# EEPROM_Programmer.net
KiCad netlist of a schematic drawn in Altium Designer
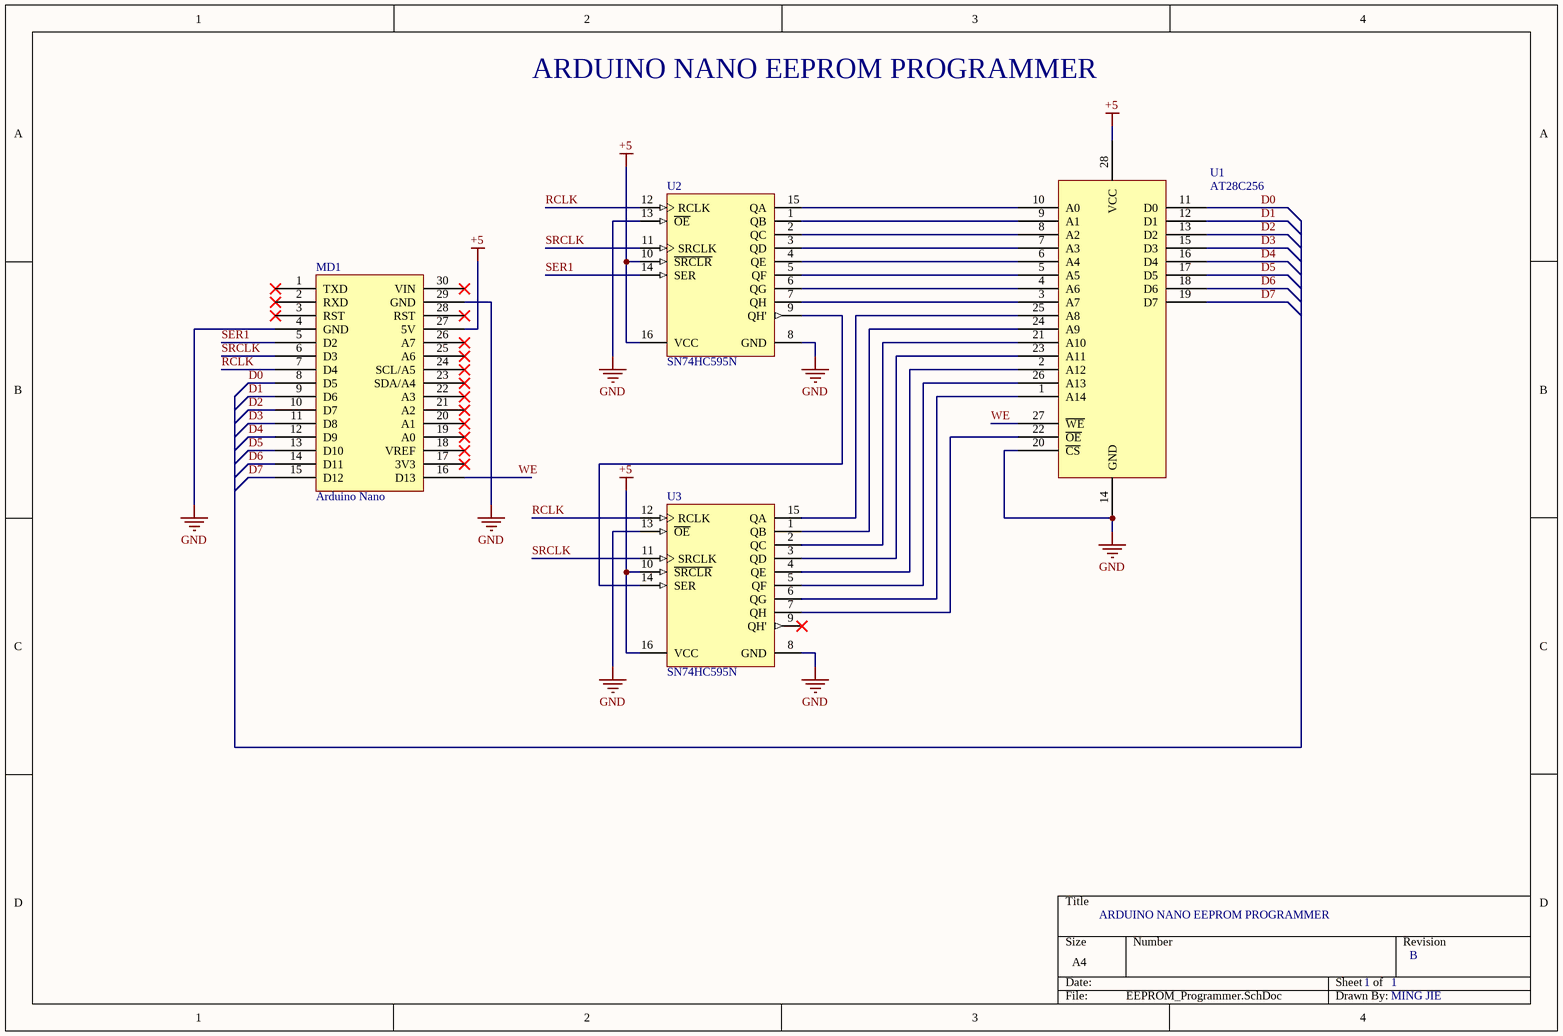
[diagram p0: EEPROM_Programmer.SchDoc]

(export (version "E")
  (design (tool "Eeschema 10.0.6"))
  (components
    (comp (ref "MD1")
      (value "Arduino Nano")
      (footprint "ARDUINO_NANO")
      (description "Arduino Nano board")
      (libsource (lib "6502_lib") (part "Arduino_Nano"))
    )
    (comp (ref "U1")
      (value "AT28C256")
      (footprint "DIP_28")
      (description "Paged Parallel EEPROM AT28C256")
      (libsource (lib "6502_lib") (part "AT28C256"))
    )
    (comp (ref "U2")
      (value "SN74HC595N")
      (footprint "N0016A")
      (description "8-Bit Shift Registers With 3-State Output Registers, N0016A, TUBE")
      (fields
        (field (name "GENERIC PART NUMBER") "SN74HC595")
        (field (name "MANUFACTURER") "Texas Instruments")
      )
      (libsource (lib "Altium Content Vault") (part "TI-SN74XHCT595X_SN74LV595A-16"))
    )
    (comp (ref "U3")
      (value "SN74HC595N")
      (footprint "N0016A")
      (description "8-Bit Shift Registers With 3-State Output Registers, N0016A, TUBE")
      (fields
        (field (name "GENERIC PART NUMBER") "SN74HC595")
        (field (name "MANUFACTURER") "Texas Instruments")
      )
      (libsource (lib "Altium Content Vault") (part "TI-SN74XHCT595X_SN74LV595A-16"))
    )
  )
  (nets
    (net (code "1") (name "+5") (class "Default")
      (node (ref "MD1") (pin "27") (pinfunction "5V_27") (pintype "passive"))
      (node (ref "U1") (pin "28") (pinfunction "VCC_28") (pintype "passive"))
      (node (ref "U2") (pin "10") (pinfunction "~{SRCLR}_10") (pintype "input"))
      (node (ref "U2") (pin "16") (pinfunction "VCC_16") (pintype "power_in"))
      (node (ref "U3") (pin "10") (pinfunction "~{SRCLR}_10") (pintype "input"))
      (node (ref "U3") (pin "16") (pinfunction "VCC_16") (pintype "power_in"))
    )
    (net (code "2") (name "/D0") (class "Default")
      (node (ref "MD1") (pin "8") (pinfunction "D5_8") (pintype "passive"))
      (node (ref "U1") (pin "11") (pinfunction "D0_11") (pintype "passive"))
    )
    (net (code "3") (name "/D1") (class "Default")
      (node (ref "MD1") (pin "9") (pinfunction "D6_9") (pintype "passive"))
      (node (ref "U1") (pin "12") (pinfunction "D1_12") (pintype "passive"))
    )
    (net (code "4") (name "/D2") (class "Default")
      (node (ref "MD1") (pin "10") (pinfunction "D7_10") (pintype "passive"))
      (node (ref "U1") (pin "13") (pinfunction "D2_13") (pintype "passive"))
    )
    (net (code "5") (name "/D3") (class "Default")
      (node (ref "MD1") (pin "11") (pinfunction "D8_11") (pintype "passive"))
      (node (ref "U1") (pin "15") (pinfunction "D3_15") (pintype "passive"))
    )
    (net (code "6") (name "/D4") (class "Default")
      (node (ref "MD1") (pin "12") (pinfunction "D9_12") (pintype "passive"))
      (node (ref "U1") (pin "16") (pinfunction "D4_16") (pintype "passive"))
    )
    (net (code "7") (name "/D5") (class "Default")
      (node (ref "MD1") (pin "13") (pinfunction "D10_13") (pintype "passive"))
      (node (ref "U1") (pin "17") (pinfunction "D5_17") (pintype "passive"))
    )
    (net (code "8") (name "/D6") (class "Default")
      (node (ref "MD1") (pin "14") (pinfunction "D11_14") (pintype "passive"))
      (node (ref "U1") (pin "18") (pinfunction "D6_18") (pintype "passive"))
    )
    (net (code "9") (name "/D7") (class "Default")
      (node (ref "MD1") (pin "15") (pinfunction "D12_15") (pintype "passive"))
      (node (ref "U1") (pin "19") (pinfunction "D7_19") (pintype "passive"))
    )
    (net (code "10") (name "/RCLK") (class "Default")
      (node (ref "MD1") (pin "7") (pinfunction "D4_7") (pintype "passive"))
      (node (ref "U2") (pin "12") (pinfunction "RCLK_12") (pintype "input"))
      (node (ref "U3") (pin "12") (pinfunction "RCLK_12") (pintype "input"))
    )
    (net (code "11") (name "/SER1") (class "Default")
      (node (ref "MD1") (pin "5") (pinfunction "D2_5") (pintype "passive"))
      (node (ref "U2") (pin "14") (pinfunction "SER_14") (pintype "input"))
    )
    (net (code "12") (name "/SRCLK") (class "Default")
      (node (ref "MD1") (pin "6") (pinfunction "D3_6") (pintype "passive"))
      (node (ref "U2") (pin "11") (pinfunction "SRCLK_11") (pintype "input"))
      (node (ref "U3") (pin "11") (pinfunction "SRCLK_11") (pintype "input"))
    )
    (net (code "13") (name "/WE") (class "Default")
      (node (ref "MD1") (pin "16") (pinfunction "D13_16") (pintype "passive"))
      (node (ref "U1") (pin "27") (pinfunction "~{WE}_27") (pintype "passive"))
    )
    (net (code "14") (name "GND") (class "Default")
      (node (ref "MD1") (pin "29") (pinfunction "GND_29") (pintype "passive"))
      (node (ref "MD1") (pin "4") (pinfunction "GND_4") (pintype "passive"))
      (node (ref "U1") (pin "14") (pinfunction "GND_14") (pintype "passive"))
      (node (ref "U1") (pin "20") (pinfunction "~{CS}_20") (pintype "passive"))
      (node (ref "U2") (pin "13") (pinfunction "~{OE}_13") (pintype "input"))
      (node (ref "U2") (pin "8") (pinfunction "GND_8") (pintype "power_in"))
      (node (ref "U3") (pin "13") (pinfunction "~{OE}_13") (pintype "input"))
      (node (ref "U3") (pin "8") (pinfunction "GND_8") (pintype "power_in"))
    )
    (net (code "15") (name "Net-(U1-A0)") (class "Default")
      (node (ref "U1") (pin "10") (pinfunction "A0_10") (pintype "passive"))
      (node (ref "U2") (pin "15") (pinfunction "QA_15") (pintype "tri_state"))
    )
    (net (code "16") (name "Net-(U1-A1)") (class "Default")
      (node (ref "U1") (pin "9") (pinfunction "A1_9") (pintype "passive"))
      (node (ref "U2") (pin "1") (pinfunction "QB_1") (pintype "tri_state"))
    )
    (net (code "17") (name "Net-(U1-A2)") (class "Default")
      (node (ref "U1") (pin "8") (pinfunction "A2_8") (pintype "passive"))
      (node (ref "U2") (pin "2") (pinfunction "QC_2") (pintype "tri_state"))
    )
    (net (code "18") (name "Net-(U1-A3)") (class "Default")
      (node (ref "U1") (pin "7") (pinfunction "A3_7") (pintype "passive"))
      (node (ref "U2") (pin "3") (pinfunction "QD_3") (pintype "tri_state"))
    )
    (net (code "19") (name "Net-(U1-A4)") (class "Default")
      (node (ref "U1") (pin "6") (pinfunction "A4_6") (pintype "passive"))
      (node (ref "U2") (pin "4") (pinfunction "QE_4") (pintype "tri_state"))
    )
    (net (code "20") (name "Net-(U1-A5)") (class "Default")
      (node (ref "U1") (pin "5") (pinfunction "A5_5") (pintype "passive"))
      (node (ref "U2") (pin "5") (pinfunction "QF_5") (pintype "tri_state"))
    )
    (net (code "21") (name "Net-(U1-A6)") (class "Default")
      (node (ref "U1") (pin "4") (pinfunction "A6_4") (pintype "passive"))
      (node (ref "U2") (pin "6") (pinfunction "QG_6") (pintype "tri_state"))
    )
    (net (code "22") (name "Net-(U1-A7)") (class "Default")
      (node (ref "U1") (pin "3") (pinfunction "A7_3") (pintype "passive"))
      (node (ref "U2") (pin "7") (pinfunction "QH_7") (pintype "tri_state"))
    )
    (net (code "23") (name "Net-(U1-A8)") (class "Default")
      (node (ref "U1") (pin "25") (pinfunction "A8_25") (pintype "passive"))
      (node (ref "U3") (pin "15") (pinfunction "QA_15") (pintype "tri_state"))
    )
    (net (code "24") (name "Net-(U1-A9)") (class "Default")
      (node (ref "U1") (pin "24") (pinfunction "A9_24") (pintype "passive"))
      (node (ref "U3") (pin "1") (pinfunction "QB_1") (pintype "tri_state"))
    )
    (net (code "25") (name "Net-(U1-A10)") (class "Default")
      (node (ref "U1") (pin "21") (pinfunction "A10_21") (pintype "passive"))
      (node (ref "U3") (pin "2") (pinfunction "QC_2") (pintype "tri_state"))
    )
    (net (code "26") (name "Net-(U1-A11)") (class "Default")
      (node (ref "U1") (pin "23") (pinfunction "A11_23") (pintype "passive"))
      (node (ref "U3") (pin "3") (pinfunction "QD_3") (pintype "tri_state"))
    )
    (net (code "27") (name "Net-(U1-A12)") (class "Default")
      (node (ref "U1") (pin "2") (pinfunction "A12_2") (pintype "passive"))
      (node (ref "U3") (pin "4") (pinfunction "QE_4") (pintype "tri_state"))
    )
    (net (code "28") (name "Net-(U1-A13)") (class "Default")
      (node (ref "U1") (pin "26") (pinfunction "A13_26") (pintype "passive"))
      (node (ref "U3") (pin "5") (pinfunction "QF_5") (pintype "tri_state"))
    )
    (net (code "29") (name "Net-(U1-A14)") (class "Default")
      (node (ref "U1") (pin "1") (pinfunction "A14_1") (pintype "passive"))
      (node (ref "U3") (pin "6") (pinfunction "QG_6") (pintype "tri_state"))
    )
    (net (code "30") (name "Net-(U1-~{OE})") (class "Default")
      (node (ref "U1") (pin "22") (pinfunction "~{OE}_22") (pintype "passive"))
      (node (ref "U3") (pin "7") (pinfunction "QH_7") (pintype "tri_state"))
    )
    (net (code "31") (name "Net-(U2-QH')") (class "Default")
      (node (ref "U2") (pin "9") (pinfunction "QH'_9") (pintype "output"))
      (node (ref "U3") (pin "14") (pinfunction "SER_14") (pintype "input"))
    )
    (net (code "32") (name "unconnected-(MD1-3V3-Pad17)") (class "Default")
      (node (ref "MD1") (pin "17") (pinfunction "3V3_17") (pintype "passive+no_connect"))
    )
    (net (code "33") (name "unconnected-(MD1-A0-Pad19)") (class "Default")
      (node (ref "MD1") (pin "19") (pinfunction "A0_19") (pintype "passive+no_connect"))
    )
    (net (code "34") (name "unconnected-(MD1-A1-Pad20)") (class "Default")
      (node (ref "MD1") (pin "20") (pinfunction "A1_20") (pintype "passive+no_connect"))
    )
    (net (code "35") (name "unconnected-(MD1-A2-Pad21)") (class "Default")
      (node (ref "MD1") (pin "21") (pinfunction "A2_21") (pintype "passive+no_connect"))
    )
    (net (code "36") (name "unconnected-(MD1-A3-Pad22)") (class "Default")
      (node (ref "MD1") (pin "22") (pinfunction "A3_22") (pintype "passive+no_connect"))
    )
    (net (code "37") (name "unconnected-(MD1-A6-Pad25)") (class "Default")
      (node (ref "MD1") (pin "25") (pinfunction "A6_25") (pintype "passive+no_connect"))
    )
    (net (code "38") (name "unconnected-(MD1-A7-Pad26)") (class "Default")
      (node (ref "MD1") (pin "26") (pinfunction "A7_26") (pintype "passive+no_connect"))
    )
    (net (code "39") (name "unconnected-(MD1-RST-Pad3)") (class "Default")
      (node (ref "MD1") (pin "3") (pinfunction "RST_3") (pintype "passive+no_connect"))
    )
    (net (code "40") (name "unconnected-(MD1-RST-Pad28)") (class "Default")
      (node (ref "MD1") (pin "28") (pinfunction "RST_28") (pintype "passive+no_connect"))
    )
    (net (code "41") (name "unconnected-(MD1-RXD-Pad2)") (class "Default")
      (node (ref "MD1") (pin "2") (pinfunction "RXD_2") (pintype "passive+no_connect"))
    )
    (net (code "42") (name "unconnected-(MD1-SCL{slash}A5-Pad24)") (class "Default")
      (node (ref "MD1") (pin "24") (pinfunction "SCL/A5_24") (pintype "passive+no_connect"))
    )
    (net (code "43") (name "unconnected-(MD1-SDA{slash}A4-Pad23)") (class "Default")
      (node (ref "MD1") (pin "23") (pinfunction "SDA/A4_23") (pintype "passive+no_connect"))
    )
    (net (code "44") (name "unconnected-(MD1-TXD-Pad1)") (class "Default")
      (node (ref "MD1") (pin "1") (pinfunction "TXD_1") (pintype "passive+no_connect"))
    )
    (net (code "45") (name "unconnected-(MD1-VIN-Pad30)") (class "Default")
      (node (ref "MD1") (pin "30") (pinfunction "VIN_30") (pintype "passive+no_connect"))
    )
    (net (code "46") (name "unconnected-(MD1-VREF-Pad18)") (class "Default")
      (node (ref "MD1") (pin "18") (pinfunction "VREF_18") (pintype "passive+no_connect"))
    )
    (net (code "47") (name "unconnected-(U3-QH'-Pad9)") (class "Default")
      (node (ref "U3") (pin "9") (pinfunction "QH'_9") (pintype "output+no_connect"))
    )
  )
)
